# Top_Sheet.net
KiCad netlist of a schematic drawn in Altium Designer
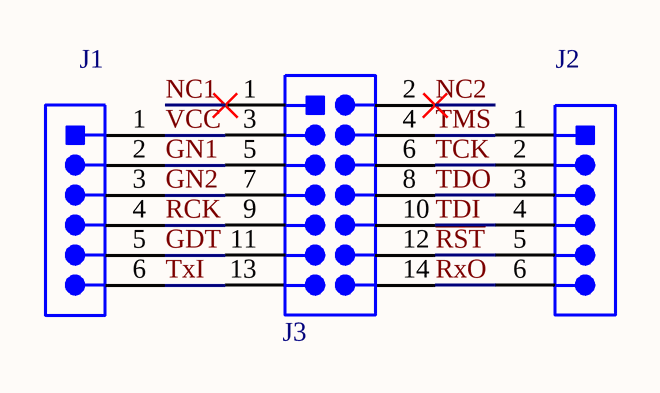
[diagram p0: Top Sheet.SchDoc]

(export (version "E")
  (design (tool "Eeschema 10.0.6"))
  (components
    (comp (ref "J1")
      (value "6 contacts Male header")
      (footprint "PH1-06-UA")
      (description "Connector Male Header 1X6 6contacts 0.100in pitch Gold Flash")
      (fields (field (name "MANUFACTURER") "Adam Tech"))
      (libsource (lib "") (part "Header 1X6_1"))
    )
    (comp (ref "J2")
      (value "6 contacts Male header")
      (footprint "PH1-06-UA")
      (description "Connector Male Header 1X6 6contacts 0.100in pitch Gold Flash")
      (fields (field (name "MANUFACTURER") "Adam Tech"))
      (libsource (lib "Connectors") (part "Header 1X6"))
    )
    (comp (ref "J3")
      (value "STDC14 Debug Connector")
      (footprint "FTSH-107-01-F-DV-K PLUGOUT")
      (description "STDC14 Debug Connector (ST Micro extension to the Cortex 10 Pin), 0.050\" (1.27mm) Pitch")
      (fields (field (name "MANUFACTURER") "Samtec"))
      (libsource (lib "Connectors") (part "STDC14"))
    )
  )
  (nets
    (net (code "1") (name "/GDT") (class "Default")
      (node (ref "J1") (pin "5") (pinfunction "5_5") (pintype "passive"))
      (node (ref "J3") (pin "11") (pinfunction "GNDDetect_11") (pintype "power_in"))
    )
    (net (code "2") (name "/GN1") (class "Default")
      (node (ref "J1") (pin "2") (pinfunction "2_2") (pintype "passive"))
      (node (ref "J3") (pin "5") (pinfunction "GND_5") (pintype "power_in"))
    )
    (net (code "3") (name "/GN2") (class "Default")
      (node (ref "J1") (pin "3") (pinfunction "3_3") (pintype "passive"))
      (node (ref "J3") (pin "7") (pinfunction "GND_7") (pintype "power_in"))
    )
    (net (code "4") (name "/NC1") (class "Default")
      (node (ref "J3") (pin "1") (pinfunction "Reserved_1") (pintype "passive+no_connect"))
    )
    (net (code "5") (name "/NC2") (class "Default")
      (node (ref "J3") (pin "2") (pinfunction "Reserved_2") (pintype "passive+no_connect"))
    )
    (net (code "6") (name "/RCK") (class "Default")
      (node (ref "J1") (pin "4") (pinfunction "4_4") (pintype "passive"))
      (node (ref "J3") (pin "9") (pinfunction "RCLK_9") (pintype "passive"))
    )
    (net (code "7") (name "/RST") (class "Default")
      (node (ref "J2") (pin "5") (pinfunction "5_5") (pintype "passive"))
      (node (ref "J3") (pin "12") (pinfunction "RESET_12") (pintype "passive"))
    )
    (net (code "8") (name "/RxO") (class "Default")
      (node (ref "J2") (pin "6") (pinfunction "6_6") (pintype "passive"))
      (node (ref "J3") (pin "14") (pinfunction "RxD_14") (pintype "passive"))
    )
    (net (code "9") (name "/TCK") (class "Default")
      (node (ref "J2") (pin "2") (pinfunction "2_2") (pintype "passive"))
      (node (ref "J3") (pin "6") (pinfunction "SWDCLK/TCK_6") (pintype "passive"))
    )
    (net (code "10") (name "/TDI") (class "Default")
      (node (ref "J2") (pin "4") (pinfunction "4_4") (pintype "passive"))
      (node (ref "J3") (pin "10") (pinfunction "NC/TDI_10") (pintype "passive"))
    )
    (net (code "11") (name "/TDO") (class "Default")
      (node (ref "J2") (pin "3") (pinfunction "3_3") (pintype "passive"))
      (node (ref "J3") (pin "8") (pinfunction "SWO/TDO_8") (pintype "passive"))
    )
    (net (code "12") (name "/TMS") (class "Default")
      (node (ref "J2") (pin "1") (pinfunction "1_1") (pintype "passive"))
      (node (ref "J3") (pin "4") (pinfunction "SWDIO/TMS_4") (pintype "passive"))
    )
    (net (code "13") (name "/TxI") (class "Default")
      (node (ref "J1") (pin "6") (pinfunction "6_6") (pintype "passive"))
      (node (ref "J3") (pin "13") (pinfunction "TxD_13") (pintype "passive"))
    )
    (net (code "14") (name "/VCC") (class "Default")
      (node (ref "J1") (pin "1") (pinfunction "1_1") (pintype "passive"))
      (node (ref "J3") (pin "3") (pinfunction "VCC_3") (pintype "power_in"))
    )
  )
)
